# battery_board_connector.net
KiCad netlist of a schematic drawn in EAGLE
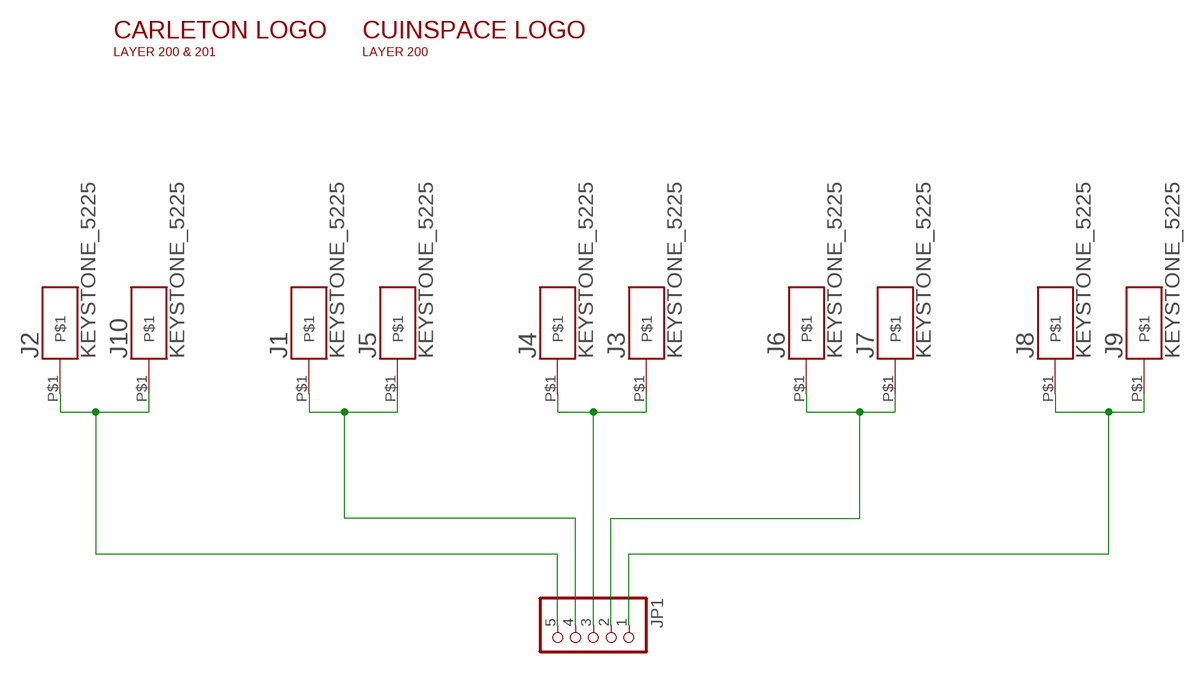
[diagram p0: schematic, sheet 1]

(export (version "E")
  (design (tool "Eeschema 10.0.6"))
  (components
    (comp (ref "J1")
      (value "KEYSTONE_5225")
      (footprint "eagle-import:KEYSTONE_5225")
      (libsource (lib "eagle-import") (part "KEYSTONE_5225"))
    )
    (comp (ref "J2")
      (value "KEYSTONE_5225")
      (footprint "eagle-import:KEYSTONE_5225")
      (libsource (lib "eagle-import") (part "KEYSTONE_5225"))
    )
    (comp (ref "J3")
      (value "KEYSTONE_5225")
      (footprint "eagle-import:KEYSTONE_5225")
      (libsource (lib "eagle-import") (part "KEYSTONE_5225"))
    )
    (comp (ref "J4")
      (value "KEYSTONE_5225")
      (footprint "eagle-import:KEYSTONE_5225")
      (libsource (lib "eagle-import") (part "KEYSTONE_5225"))
    )
    (comp (ref "J5")
      (value "KEYSTONE_5225")
      (footprint "eagle-import:KEYSTONE_5225")
      (libsource (lib "eagle-import") (part "KEYSTONE_5225"))
    )
    (comp (ref "J6")
      (value "KEYSTONE_5225")
      (footprint "eagle-import:KEYSTONE_5225")
      (libsource (lib "eagle-import") (part "KEYSTONE_5225"))
    )
    (comp (ref "J7")
      (value "KEYSTONE_5225")
      (footprint "eagle-import:KEYSTONE_5225")
      (libsource (lib "eagle-import") (part "KEYSTONE_5225"))
    )
    (comp (ref "J8")
      (value "KEYSTONE_5225")
      (footprint "eagle-import:KEYSTONE_5225")
      (libsource (lib "eagle-import") (part "KEYSTONE_5225"))
    )
    (comp (ref "J9")
      (value "KEYSTONE_5225")
      (footprint "eagle-import:KEYSTONE_5225")
      (libsource (lib "eagle-import") (part "KEYSTONE_5225"))
    )
    (comp (ref "J10")
      (value "KEYSTONE_5225")
      (footprint "eagle-import:KEYSTONE_5225")
      (libsource (lib "eagle-import") (part "KEYSTONE_5225"))
    )
    (comp (ref "JP1")
      (value "PINHD-1X5")
      (footprint "eagle-import:1X05")
      (libsource (lib "eagle-import") (part "PINHD-1X5"))
    )
    (comp (ref "U$1")
      (value "INSPACE3CM")
      (footprint "eagle-import:INSPACE_3CM")
      (libsource (lib "eagle-import") (part "INSPACE3CM"))
    )
    (comp (ref "U$2")
      (value "CARLETON3CM")
      (footprint "eagle-import:CARLETONU_3CM")
      (libsource (lib "eagle-import") (part "CARLETON3CM"))
    )
  )
  (nets
    (net (code "1") (name "Net-(J1-PadP$1)") (class "Default")
      (node (ref "J1") (pin "P$1") (pinfunction "P$1_P$1") (pintype "bidirectional"))
      (node (ref "J5") (pin "P$1") (pinfunction "P$1_P$1") (pintype "bidirectional"))
      (node (ref "JP1") (pin "4") (pinfunction "4_4") (pintype "passive"))
    )
    (net (code "2") (name "Net-(J3-PadP$1)") (class "Default")
      (node (ref "J3") (pin "P$1") (pinfunction "P$1_P$1") (pintype "bidirectional"))
      (node (ref "J4") (pin "P$1") (pinfunction "P$1_P$1") (pintype "bidirectional"))
      (node (ref "JP1") (pin "3") (pinfunction "3_3") (pintype "passive"))
    )
    (net (code "3") (name "Net-(J6-PadP$1)") (class "Default")
      (node (ref "J6") (pin "P$1") (pinfunction "P$1_P$1") (pintype "bidirectional"))
      (node (ref "J7") (pin "P$1") (pinfunction "P$1_P$1") (pintype "bidirectional"))
      (node (ref "JP1") (pin "2") (pinfunction "2_2") (pintype "passive"))
    )
    (net (code "4") (name "Net-(J8-PadP$1)") (class "Default")
      (node (ref "J8") (pin "P$1") (pinfunction "P$1_P$1") (pintype "bidirectional"))
      (node (ref "J9") (pin "P$1") (pinfunction "P$1_P$1") (pintype "bidirectional"))
      (node (ref "JP1") (pin "1") (pinfunction "1_1") (pintype "passive"))
    )
    (net (code "5") (name "Net-(J10-PadP$1)") (class "Default")
      (node (ref "J10") (pin "P$1") (pinfunction "P$1_P$1") (pintype "bidirectional"))
      (node (ref "J2") (pin "P$1") (pinfunction "P$1_P$1") (pintype "bidirectional"))
      (node (ref "JP1") (pin "5") (pinfunction "5_5") (pintype "passive"))
    )
  )
)
